# keypad.net
KiCad netlist of a schematic drawn in EAGLE
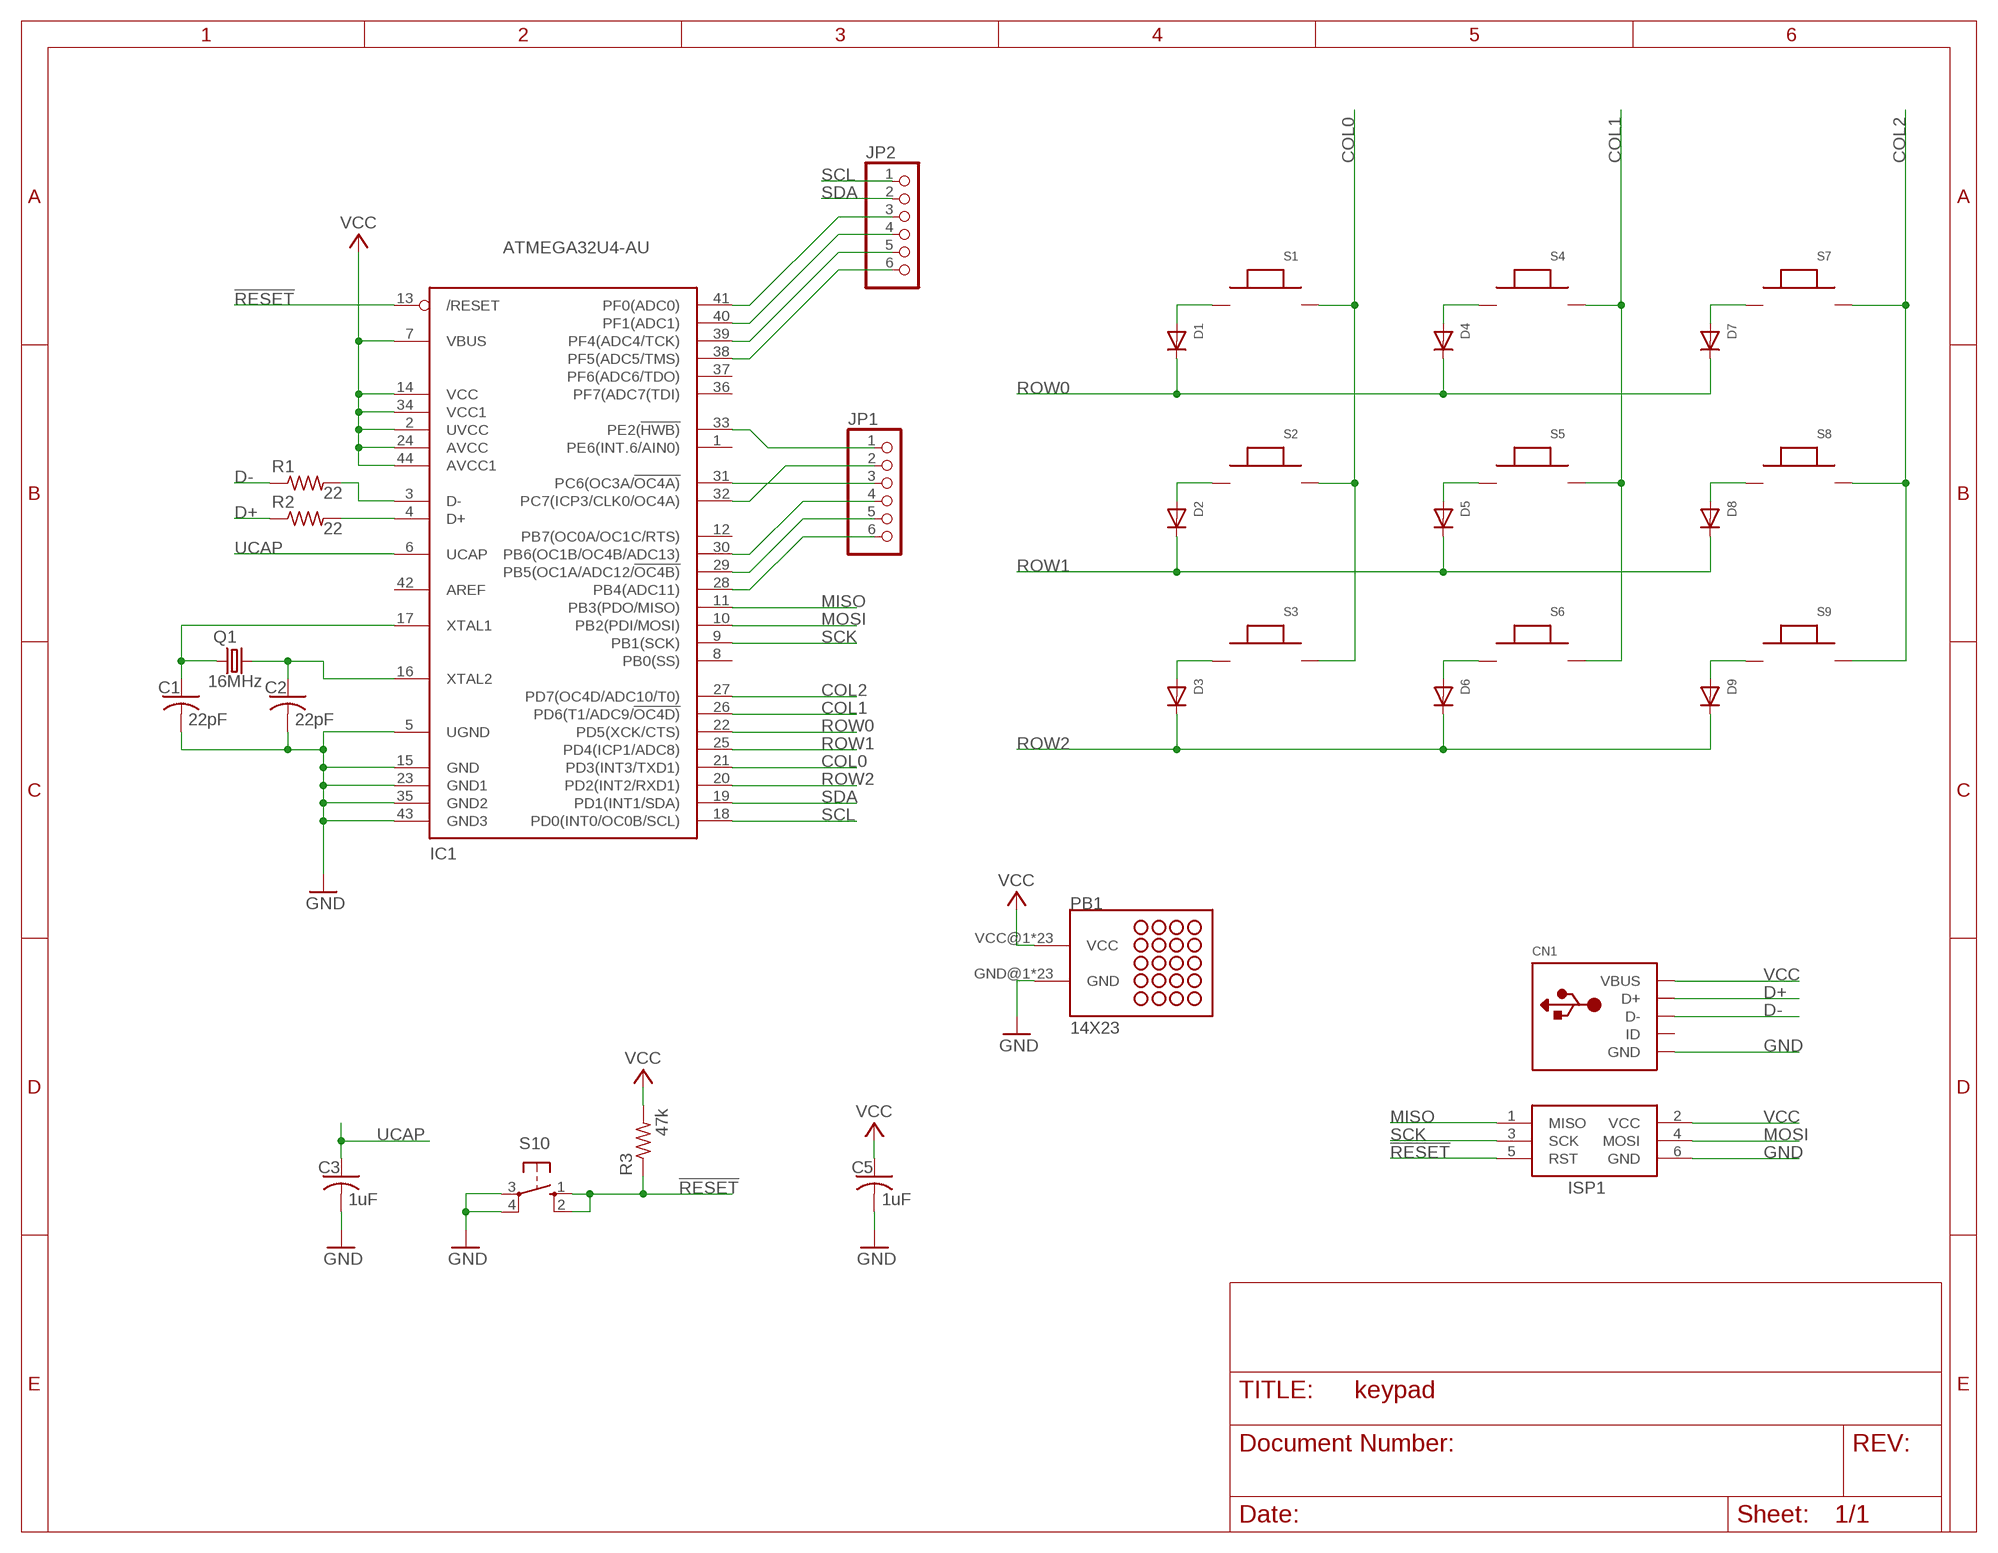
[diagram p0: schematic, sheet 1]

(export (version "E")
  (design (tool "Eeschema 10.0.6"))
  (components
    (comp (ref "C1")
      (value "22pF")
      (footprint "eagle-import:C0805")
      (libsource (lib "eagle-import") (part "C-USC0805"))
    )
    (comp (ref "C2")
      (value "22pF")
      (footprint "eagle-import:C0805")
      (libsource (lib "eagle-import") (part "C-USC0805"))
    )
    (comp (ref "C3")
      (value "1uF")
      (footprint "eagle-import:C0805")
      (libsource (lib "eagle-import") (part "C-USC0805"))
    )
    (comp (ref "C5")
      (value "1uF")
      (footprint "eagle-import:C0805")
      (libsource (lib "eagle-import") (part "C-USC0805"))
    )
    (comp (ref "CN1")
      (value "USBMOLEX")
      (footprint "eagle-import:USB-MINIB-THM-MOLEX")
      (libsource (lib "eagle-import") (part "USBMOLEX"))
    )
    (comp (ref "D1")
      (value "DIODESOD-123")
      (footprint "eagle-import:SOD-123")
      (libsource (lib "eagle-import") (part "DIODESOD-123"))
    )
    (comp (ref "D2")
      (value "DIODESOD-123")
      (footprint "eagle-import:SOD-123")
      (libsource (lib "eagle-import") (part "DIODESOD-123"))
    )
    (comp (ref "D3")
      (value "DIODESOD-123")
      (footprint "eagle-import:SOD-123")
      (libsource (lib "eagle-import") (part "DIODESOD-123"))
    )
    (comp (ref "D4")
      (value "DIODESOD-123")
      (footprint "eagle-import:SOD-123")
      (libsource (lib "eagle-import") (part "DIODESOD-123"))
    )
    (comp (ref "D5")
      (value "DIODESOD-123")
      (footprint "eagle-import:SOD-123")
      (libsource (lib "eagle-import") (part "DIODESOD-123"))
    )
    (comp (ref "D6")
      (value "DIODESOD-123")
      (footprint "eagle-import:SOD-123")
      (libsource (lib "eagle-import") (part "DIODESOD-123"))
    )
    (comp (ref "D7")
      (value "DIODESOD-123")
      (footprint "eagle-import:SOD-123")
      (libsource (lib "eagle-import") (part "DIODESOD-123"))
    )
    (comp (ref "D8")
      (value "DIODESOD-123")
      (footprint "eagle-import:SOD-123")
      (libsource (lib "eagle-import") (part "DIODESOD-123"))
    )
    (comp (ref "D9")
      (value "DIODESOD-123")
      (footprint "eagle-import:SOD-123")
      (libsource (lib "eagle-import") (part "DIODESOD-123"))
    )
    (comp (ref "IC1")
      (value "ATMEGA32U4-AU")
      (footprint "eagle-import:TQFP44")
      (libsource (lib "eagle-import") (part "ATMEGA32U4-AU"))
    )
    (comp (ref "ISP1")
      (value "AVRISP-6")
      (footprint "eagle-import:AVRISP")
      (libsource (lib "eagle-import") (part "AVRISP-6"))
    )
    (comp (ref "JP1")
      (value "PINHD-1X6")
      (footprint "eagle-import:1X06")
      (libsource (lib "eagle-import") (part "PINHD-1X6"))
    )
    (comp (ref "JP2")
      (value "PINHD-1X6")
      (footprint "eagle-import:1X06")
      (libsource (lib "eagle-import") (part "PINHD-1X6"))
    )
    (comp (ref "PB1")
      (value "14X23")
      (footprint "eagle-import:14X23")
      (libsource (lib "eagle-import") (part "14X23"))
    )
    (comp (ref "Q1")
      (value "16MHz")
      (footprint "eagle-import:HC49_S")
      (libsource (lib "eagle-import") (part "CRYSTALHC49S"))
    )
    (comp (ref "R1")
      (value "22")
      (footprint "eagle-import:R0805")
      (libsource (lib "eagle-import") (part "R-US_R0805"))
    )
    (comp (ref "R2")
      (value "22")
      (footprint "eagle-import:R0805")
      (libsource (lib "eagle-import") (part "R-US_R0805"))
    )
    (comp (ref "R3")
      (value "47k")
      (footprint "eagle-import:R0805")
      (libsource (lib "eagle-import") (part "R-US_R0805"))
    )
    (comp (ref "S1")
      (value "MX-SMD")
      (footprint "eagle-import:MX_SMD")
      (libsource (lib "eagle-import") (part "MX-SMD"))
    )
    (comp (ref "S2")
      (value "MX-SMD")
      (footprint "eagle-import:MX_SMD")
      (libsource (lib "eagle-import") (part "MX-SMD"))
    )
    (comp (ref "S3")
      (value "MX-SMD")
      (footprint "eagle-import:MX_SMD")
      (libsource (lib "eagle-import") (part "MX-SMD"))
    )
    (comp (ref "S4")
      (value "MX-SMD")
      (footprint "eagle-import:MX_SMD")
      (libsource (lib "eagle-import") (part "MX-SMD"))
    )
    (comp (ref "S5")
      (value "MX-SMD")
      (footprint "eagle-import:MX_SMD")
      (libsource (lib "eagle-import") (part "MX-SMD"))
    )
    (comp (ref "S6")
      (value "MX-SMD")
      (footprint "eagle-import:MX_SMD")
      (libsource (lib "eagle-import") (part "MX-SMD"))
    )
    (comp (ref "S7")
      (value "MX-SMD")
      (footprint "eagle-import:MX_SMD")
      (libsource (lib "eagle-import") (part "MX-SMD"))
    )
    (comp (ref "S8")
      (value "MX-SMD")
      (footprint "eagle-import:MX_SMD")
      (libsource (lib "eagle-import") (part "MX-SMD"))
    )
    (comp (ref "S9")
      (value "MX-SMD")
      (footprint "eagle-import:MX_SMD")
      (libsource (lib "eagle-import") (part "MX-SMD"))
    )
    (comp (ref "S10")
      (value "10-XX")
      (footprint "eagle-import:B3F-10XX")
      (fields (field (name "MPN") "B3F-1000"))
      (libsource (lib "eagle-import") (part "10-XX"))
    )
  )
  (nets
    (net (code "1") (name "/COL0") (class "Default")
      (node (ref "IC1") (pin "21") (pinfunction "PD3(INT3/TXD1)_21") (pintype "bidirectional"))
      (node (ref "S1") (pin "P$2") (pinfunction "P$2_P$2") (pintype "bidirectional"))
      (node (ref "S2") (pin "P$2") (pinfunction "P$2_P$2") (pintype "bidirectional"))
      (node (ref "S3") (pin "P$2") (pinfunction "P$2_P$2") (pintype "bidirectional"))
    )
    (net (code "2") (name "/COL1") (class "Default")
      (node (ref "IC1") (pin "26") (pinfunction "PD6(T1/ADC9/~{OC4D})_26") (pintype "bidirectional"))
      (node (ref "S4") (pin "P$2") (pinfunction "P$2_P$2") (pintype "bidirectional"))
      (node (ref "S5") (pin "P$2") (pinfunction "P$2_P$2") (pintype "bidirectional"))
      (node (ref "S6") (pin "P$2") (pinfunction "P$2_P$2") (pintype "bidirectional"))
    )
    (net (code "3") (name "/COL2") (class "Default")
      (node (ref "IC1") (pin "27") (pinfunction "PD7(OC4D/ADC10/T0)_27") (pintype "bidirectional"))
      (node (ref "S7") (pin "P$2") (pinfunction "P$2_P$2") (pintype "bidirectional"))
      (node (ref "S8") (pin "P$2") (pinfunction "P$2_P$2") (pintype "bidirectional"))
      (node (ref "S9") (pin "P$2") (pinfunction "P$2_P$2") (pintype "bidirectional"))
    )
    (net (code "4") (name "/D+") (class "Default")
      (node (ref "CN1") (pin "D+") (pinfunction "D+_D+") (pintype "bidirectional"))
      (node (ref "R2") (pin "1") (pinfunction "1_1") (pintype "passive"))
    )
    (net (code "5") (name "/D-") (class "Default")
      (node (ref "CN1") (pin "D-") (pinfunction "D-_D-") (pintype "bidirectional"))
      (node (ref "R1") (pin "1") (pinfunction "1_1") (pintype "passive"))
    )
    (net (code "6") (name "/MISO") (class "Default")
      (node (ref "IC1") (pin "11") (pinfunction "PB3(PDO/MISO)_11") (pintype "bidirectional"))
      (node (ref "ISP1") (pin "1") (pinfunction "MISO_1") (pintype "input"))
    )
    (net (code "7") (name "/MOSI") (class "Default")
      (node (ref "IC1") (pin "10") (pinfunction "PB2(PDI/MOSI)_10") (pintype "bidirectional"))
      (node (ref "ISP1") (pin "4") (pinfunction "MOSI_4") (pintype "output"))
    )
    (net (code "8") (name "/ROW0") (class "Default")
      (node (ref "D1") (pin "C") (pinfunction "C_C") (pintype "passive"))
      (node (ref "D4") (pin "C") (pinfunction "C_C") (pintype "passive"))
      (node (ref "D7") (pin "C") (pinfunction "C_C") (pintype "passive"))
      (node (ref "IC1") (pin "22") (pinfunction "PD5(XCK/CTS)_22") (pintype "bidirectional"))
    )
    (net (code "9") (name "/ROW1") (class "Default")
      (node (ref "D2") (pin "C") (pinfunction "C_C") (pintype "passive"))
      (node (ref "D5") (pin "C") (pinfunction "C_C") (pintype "passive"))
      (node (ref "D8") (pin "C") (pinfunction "C_C") (pintype "passive"))
      (node (ref "IC1") (pin "25") (pinfunction "PD4(ICP1/ADC8)_25") (pintype "bidirectional"))
    )
    (net (code "10") (name "/ROW2") (class "Default")
      (node (ref "D3") (pin "C") (pinfunction "C_C") (pintype "passive"))
      (node (ref "D6") (pin "C") (pinfunction "C_C") (pintype "passive"))
      (node (ref "D9") (pin "C") (pinfunction "C_C") (pintype "passive"))
      (node (ref "IC1") (pin "20") (pinfunction "PD2(INT2/RXD1)_20") (pintype "bidirectional"))
    )
    (net (code "11") (name "/SCK") (class "Default")
      (node (ref "IC1") (pin "9") (pinfunction "PB1(SCK)_9") (pintype "bidirectional"))
      (node (ref "ISP1") (pin "3") (pinfunction "SCK_3") (pintype "output"))
    )
    (net (code "12") (name "/SCL") (class "Default")
      (node (ref "IC1") (pin "18") (pinfunction "PD0(INT0/OC0B/SCL)_18") (pintype "bidirectional"))
      (node (ref "JP2") (pin "1") (pinfunction "1_1") (pintype "passive"))
    )
    (net (code "13") (name "/SDA") (class "Default")
      (node (ref "IC1") (pin "19") (pinfunction "PD1(INT1/SDA)_19") (pintype "bidirectional"))
      (node (ref "JP2") (pin "2") (pinfunction "2_2") (pintype "passive"))
    )
    (net (code "14") (name "/UCAP") (class "Default")
      (node (ref "C3") (pin "1") (pinfunction "1_1") (pintype "passive"))
      (node (ref "IC1") (pin "6") (pinfunction "UCAP_6") (pintype "bidirectional"))
    )
    (net (code "15") (name "/~{RESET}") (class "Default")
      (node (ref "IC1") (pin "13") (pinfunction "/RESET_13") (pintype "bidirectional"))
      (node (ref "ISP1") (pin "5") (pinfunction "RST_5") (pintype "output"))
      (node (ref "R3") (pin "1") (pinfunction "1_1") (pintype "passive"))
      (node (ref "S10") (pin "1") (pinfunction "S_1") (pintype "passive"))
      (node (ref "S10") (pin "2") (pinfunction "S1_2") (pintype "passive"))
    )
    (net (code "16") (name "GND") (class "Default")
      (node (ref "C1") (pin "2") (pinfunction "2_2") (pintype "passive"))
      (node (ref "C2") (pin "2") (pinfunction "2_2") (pintype "passive"))
      (node (ref "C3") (pin "2") (pinfunction "2_2") (pintype "passive"))
      (node (ref "C5") (pin "2") (pinfunction "2_2") (pintype "passive"))
      (node (ref "CN1") (pin "GND") (pinfunction "GND_GND") (pintype "power_in"))
      (node (ref "IC1") (pin "15") (pinfunction "GND_15") (pintype "bidirectional"))
      (node (ref "IC1") (pin "23") (pinfunction "GND1_23") (pintype "bidirectional"))
      (node (ref "IC1") (pin "35") (pinfunction "GND2_35") (pintype "bidirectional"))
      (node (ref "IC1") (pin "43") (pinfunction "GND3_43") (pintype "bidirectional"))
      (node (ref "IC1") (pin "5") (pinfunction "UGND_5") (pintype "bidirectional"))
      (node (ref "ISP1") (pin "6") (pinfunction "GND_6") (pintype "power_in"))
      (node (ref "PB1") (pin "GND@1") (pinfunction "GND_GND@1") (pintype "power_in"))
      (node (ref "PB1") (pin "GND@10") (pinfunction "GND_GND@10") (pintype "power_in"))
      (node (ref "PB1") (pin "GND@11") (pinfunction "GND_GND@11") (pintype "power_in"))
      (node (ref "PB1") (pin "GND@12") (pinfunction "GND_GND@12") (pintype "power_in"))
      (node (ref "PB1") (pin "GND@13") (pinfunction "GND_GND@13") (pintype "power_in"))
      (node (ref "PB1") (pin "GND@14") (pinfunction "GND_GND@14") (pintype "power_in"))
      (node (ref "PB1") (pin "GND@15") (pinfunction "GND_GND@15") (pintype "power_in"))
      (node (ref "PB1") (pin "GND@16") (pinfunction "GND_GND@16") (pintype "power_in"))
      (node (ref "PB1") (pin "GND@17") (pinfunction "GND_GND@17") (pintype "power_in"))
      (node (ref "PB1") (pin "GND@18") (pinfunction "GND_GND@18") (pintype "power_in"))
      (node (ref "PB1") (pin "GND@19") (pinfunction "GND_GND@19") (pintype "power_in"))
      (node (ref "PB1") (pin "GND@2") (pinfunction "GND_GND@2") (pintype "power_in"))
      (node (ref "PB1") (pin "GND@20") (pinfunction "GND_GND@20") (pintype "power_in"))
      (node (ref "PB1") (pin "GND@21") (pinfunction "GND_GND@21") (pintype "power_in"))
      (node (ref "PB1") (pin "GND@22") (pinfunction "GND_GND@22") (pintype "power_in"))
      (node (ref "PB1") (pin "GND@23") (pinfunction "GND_GND@23") (pintype "power_in"))
      (node (ref "PB1") (pin "GND@3") (pinfunction "GND_GND@3") (pintype "power_in"))
      (node (ref "PB1") (pin "GND@4") (pinfunction "GND_GND@4") (pintype "power_in"))
      (node (ref "PB1") (pin "GND@5") (pinfunction "GND_GND@5") (pintype "power_in"))
      (node (ref "PB1") (pin "GND@6") (pinfunction "GND_GND@6") (pintype "power_in"))
      (node (ref "PB1") (pin "GND@7") (pinfunction "GND_GND@7") (pintype "power_in"))
      (node (ref "PB1") (pin "GND@8") (pinfunction "GND_GND@8") (pintype "power_in"))
      (node (ref "PB1") (pin "GND@9") (pinfunction "GND_GND@9") (pintype "power_in"))
      (node (ref "S10") (pin "3") (pinfunction "P_3") (pintype "passive"))
      (node (ref "S10") (pin "4") (pinfunction "P1_4") (pintype "passive"))
    )
    (net (code "17") (name "Net-(D1-PadA)") (class "Default")
      (node (ref "D1") (pin "A") (pinfunction "A_A") (pintype "passive"))
      (node (ref "S1") (pin "P$1") (pinfunction "P$1_P$1") (pintype "bidirectional"))
    )
    (net (code "18") (name "Net-(D2-PadA)") (class "Default")
      (node (ref "D2") (pin "A") (pinfunction "A_A") (pintype "passive"))
      (node (ref "S2") (pin "P$1") (pinfunction "P$1_P$1") (pintype "bidirectional"))
    )
    (net (code "19") (name "Net-(D3-PadA)") (class "Default")
      (node (ref "D3") (pin "A") (pinfunction "A_A") (pintype "passive"))
      (node (ref "S3") (pin "P$1") (pinfunction "P$1_P$1") (pintype "bidirectional"))
    )
    (net (code "20") (name "Net-(D4-PadA)") (class "Default")
      (node (ref "D4") (pin "A") (pinfunction "A_A") (pintype "passive"))
      (node (ref "S4") (pin "P$1") (pinfunction "P$1_P$1") (pintype "bidirectional"))
    )
    (net (code "21") (name "Net-(D5-PadA)") (class "Default")
      (node (ref "D5") (pin "A") (pinfunction "A_A") (pintype "passive"))
      (node (ref "S5") (pin "P$1") (pinfunction "P$1_P$1") (pintype "bidirectional"))
    )
    (net (code "22") (name "Net-(D6-PadA)") (class "Default")
      (node (ref "D6") (pin "A") (pinfunction "A_A") (pintype "passive"))
      (node (ref "S6") (pin "P$1") (pinfunction "P$1_P$1") (pintype "bidirectional"))
    )
    (net (code "23") (name "Net-(D7-PadA)") (class "Default")
      (node (ref "D7") (pin "A") (pinfunction "A_A") (pintype "passive"))
      (node (ref "S7") (pin "P$1") (pinfunction "P$1_P$1") (pintype "bidirectional"))
    )
    (net (code "24") (name "Net-(D8-PadA)") (class "Default")
      (node (ref "D8") (pin "A") (pinfunction "A_A") (pintype "passive"))
      (node (ref "S8") (pin "P$1") (pinfunction "P$1_P$1") (pintype "bidirectional"))
    )
    (net (code "25") (name "Net-(D9-PadA)") (class "Default")
      (node (ref "D9") (pin "A") (pinfunction "A_A") (pintype "passive"))
      (node (ref "S9") (pin "P$1") (pinfunction "P$1_P$1") (pintype "bidirectional"))
    )
    (net (code "26") (name "Net-(IC1-D+)") (class "Default")
      (node (ref "IC1") (pin "4") (pinfunction "D+_4") (pintype "bidirectional"))
      (node (ref "R2") (pin "2") (pinfunction "2_2") (pintype "passive"))
    )
    (net (code "27") (name "Net-(IC1-D-)") (class "Default")
      (node (ref "IC1") (pin "3") (pinfunction "D-_3") (pintype "bidirectional"))
      (node (ref "R1") (pin "2") (pinfunction "2_2") (pintype "passive"))
    )
    (net (code "28") (name "Net-(IC1-PB4(ADC11))") (class "Default")
      (node (ref "IC1") (pin "28") (pinfunction "PB4(ADC11)_28") (pintype "bidirectional"))
      (node (ref "JP1") (pin "6") (pinfunction "6_6") (pintype "passive"))
    )
    (net (code "29") (name "Net-(IC1-PB5(OC1A{slash}ADC12{slash}~{OC4B}))") (class "Default")
      (node (ref "IC1") (pin "29") (pinfunction "PB5(OC1A/ADC12/~{OC4B})_29") (pintype "bidirectional"))
      (node (ref "JP1") (pin "5") (pinfunction "5_5") (pintype "passive"))
    )
    (net (code "30") (name "Net-(IC1-PB6(OC1B{slash}OC4B{slash}ADC13))") (class "Default")
      (node (ref "IC1") (pin "30") (pinfunction "PB6(OC1B/OC4B/ADC13)_30") (pintype "bidirectional"))
      (node (ref "JP1") (pin "4") (pinfunction "4_4") (pintype "passive"))
    )
    (net (code "31") (name "Net-(IC1-PC6(OC3A{slash}~{OC4A}))") (class "Default")
      (node (ref "IC1") (pin "31") (pinfunction "PC6(OC3A/~{OC4A})_31") (pintype "bidirectional"))
      (node (ref "JP1") (pin "3") (pinfunction "3_3") (pintype "passive"))
    )
    (net (code "32") (name "Net-(IC1-PC7(ICP3{slash}CLK0{slash}OC4A))") (class "Default")
      (node (ref "IC1") (pin "32") (pinfunction "PC7(ICP3/CLK0/OC4A)_32") (pintype "bidirectional"))
      (node (ref "JP1") (pin "2") (pinfunction "2_2") (pintype "passive"))
    )
    (net (code "33") (name "Net-(IC1-PE2(~{HWB}))") (class "Default")
      (node (ref "IC1") (pin "33") (pinfunction "PE2(~{HWB})_33") (pintype "bidirectional"))
      (node (ref "JP1") (pin "1") (pinfunction "1_1") (pintype "passive"))
    )
    (net (code "34") (name "Net-(IC1-PF0(ADC0))") (class "Default")
      (node (ref "IC1") (pin "41") (pinfunction "PF0(ADC0)_41") (pintype "bidirectional"))
      (node (ref "JP2") (pin "3") (pinfunction "3_3") (pintype "passive"))
    )
    (net (code "35") (name "Net-(IC1-PF1(ADC1))") (class "Default")
      (node (ref "IC1") (pin "40") (pinfunction "PF1(ADC1)_40") (pintype "bidirectional"))
      (node (ref "JP2") (pin "4") (pinfunction "4_4") (pintype "passive"))
    )
    (net (code "36") (name "Net-(IC1-PF4(ADC4{slash}TCK))") (class "Default")
      (node (ref "IC1") (pin "39") (pinfunction "PF4(ADC4/TCK)_39") (pintype "bidirectional"))
      (node (ref "JP2") (pin "5") (pinfunction "5_5") (pintype "passive"))
    )
    (net (code "37") (name "Net-(IC1-PF5(ADC5{slash}TMS))") (class "Default")
      (node (ref "IC1") (pin "38") (pinfunction "PF5(ADC5/TMS)_38") (pintype "bidirectional"))
      (node (ref "JP2") (pin "6") (pinfunction "6_6") (pintype "passive"))
    )
    (net (code "38") (name "Net-(IC1-XTAL1)") (class "Default")
      (node (ref "C1") (pin "1") (pinfunction "1_1") (pintype "passive"))
      (node (ref "IC1") (pin "17") (pinfunction "XTAL1_17") (pintype "bidirectional"))
      (node (ref "Q1") (pin "1") (pinfunction "1_1") (pintype "passive"))
    )
    (net (code "39") (name "Net-(IC1-XTAL2)") (class "Default")
      (node (ref "C2") (pin "1") (pinfunction "1_1") (pintype "passive"))
      (node (ref "IC1") (pin "16") (pinfunction "XTAL2_16") (pintype "bidirectional"))
      (node (ref "Q1") (pin "2") (pinfunction "2_2") (pintype "passive"))
    )
    (net (code "40") (name "VCC") (class "Default")
      (node (ref "C5") (pin "1") (pinfunction "1_1") (pintype "passive"))
      (node (ref "CN1") (pin "VBUS") (pinfunction "VBUS_VBUS") (pintype "power_in"))
      (node (ref "IC1") (pin "14") (pinfunction "VCC_14") (pintype "bidirectional"))
      (node (ref "IC1") (pin "2") (pinfunction "UVCC_2") (pintype "bidirectional"))
      (node (ref "IC1") (pin "24") (pinfunction "AVCC_24") (pintype "bidirectional"))
      (node (ref "IC1") (pin "34") (pinfunction "VCC1_34") (pintype "bidirectional"))
      (node (ref "IC1") (pin "44") (pinfunction "AVCC1_44") (pintype "bidirectional"))
      (node (ref "IC1") (pin "7") (pinfunction "VBUS_7") (pintype "bidirectional"))
      (node (ref "ISP1") (pin "2") (pinfunction "VCC_2") (pintype "power_in"))
      (node (ref "PB1") (pin "VCC@1") (pinfunction "VCC_VCC@1") (pintype "power_in"))
      (node (ref "PB1") (pin "VCC@10") (pinfunction "VCC_VCC@10") (pintype "power_in"))
      (node (ref "PB1") (pin "VCC@11") (pinfunction "VCC_VCC@11") (pintype "power_in"))
      (node (ref "PB1") (pin "VCC@12") (pinfunction "VCC_VCC@12") (pintype "power_in"))
      (node (ref "PB1") (pin "VCC@13") (pinfunction "VCC_VCC@13") (pintype "power_in"))
      (node (ref "PB1") (pin "VCC@14") (pinfunction "VCC_VCC@14") (pintype "power_in"))
      (node (ref "PB1") (pin "VCC@15") (pinfunction "VCC_VCC@15") (pintype "power_in"))
      (node (ref "PB1") (pin "VCC@16") (pinfunction "VCC_VCC@16") (pintype "power_in"))
      (node (ref "PB1") (pin "VCC@17") (pinfunction "VCC_VCC@17") (pintype "power_in"))
      (node (ref "PB1") (pin "VCC@18") (pinfunction "VCC_VCC@18") (pintype "power_in"))
      (node (ref "PB1") (pin "VCC@19") (pinfunction "VCC_VCC@19") (pintype "power_in"))
      (node (ref "PB1") (pin "VCC@2") (pinfunction "VCC_VCC@2") (pintype "power_in"))
      (node (ref "PB1") (pin "VCC@20") (pinfunction "VCC_VCC@20") (pintype "power_in"))
      (node (ref "PB1") (pin "VCC@21") (pinfunction "VCC_VCC@21") (pintype "power_in"))
      (node (ref "PB1") (pin "VCC@22") (pinfunction "VCC_VCC@22") (pintype "power_in"))
      (node (ref "PB1") (pin "VCC@23") (pinfunction "VCC_VCC@23") (pintype "power_in"))
      (node (ref "PB1") (pin "VCC@3") (pinfunction "VCC_VCC@3") (pintype "power_in"))
      (node (ref "PB1") (pin "VCC@4") (pinfunction "VCC_VCC@4") (pintype "power_in"))
      (node (ref "PB1") (pin "VCC@5") (pinfunction "VCC_VCC@5") (pintype "power_in"))
      (node (ref "PB1") (pin "VCC@6") (pinfunction "VCC_VCC@6") (pintype "power_in"))
      (node (ref "PB1") (pin "VCC@7") (pinfunction "VCC_VCC@7") (pintype "power_in"))
      (node (ref "PB1") (pin "VCC@8") (pinfunction "VCC_VCC@8") (pintype "power_in"))
      (node (ref "PB1") (pin "VCC@9") (pinfunction "VCC_VCC@9") (pintype "power_in"))
      (node (ref "R3") (pin "2") (pinfunction "2_2") (pintype "passive"))
    )
    (net (code "41") (name "unconnected-(CN1-PadID)") (class "Default")
      (node (ref "CN1") (pin "ID") (pinfunction "ID_ID") (pintype "bidirectional"))
    )
    (net (code "42") (name "unconnected-(IC1-AREF-Pad42)") (class "Default")
      (node (ref "IC1") (pin "42") (pinfunction "AREF_42") (pintype "bidirectional"))
    )
    (net (code "43") (name "unconnected-(IC1-PB0(SS)-Pad8)") (class "Default")
      (node (ref "IC1") (pin "8") (pinfunction "PB0(SS)_8") (pintype "bidirectional"))
    )
    (net (code "44") (name "unconnected-(IC1-PB7(OC0A{slash}OC1C{slash}RTS)-Pad12)") (class "Default")
      (node (ref "IC1") (pin "12") (pinfunction "PB7(OC0A/OC1C/RTS)_12") (pintype "bidirectional"))
    )
    (net (code "45") (name "unconnected-(IC1-PE6(INT.6{slash}AIN0)-Pad1)") (class "Default")
      (node (ref "IC1") (pin "1") (pinfunction "PE6(INT.6/AIN0)_1") (pintype "bidirectional"))
    )
    (net (code "46") (name "unconnected-(IC1-PF6(ADC6{slash}TDO)-Pad37)") (class "Default")
      (node (ref "IC1") (pin "37") (pinfunction "PF6(ADC6/TDO)_37") (pintype "bidirectional"))
    )
    (net (code "47") (name "unconnected-(IC1-PF7(ADC7(TDI)-Pad36)") (class "Default")
      (node (ref "IC1") (pin "36") (pinfunction "PF7(ADC7(TDI)_36") (pintype "bidirectional"))
    )
  )
)
